# G021.net
KiCad netlist of a schematic drawn in EAGLE
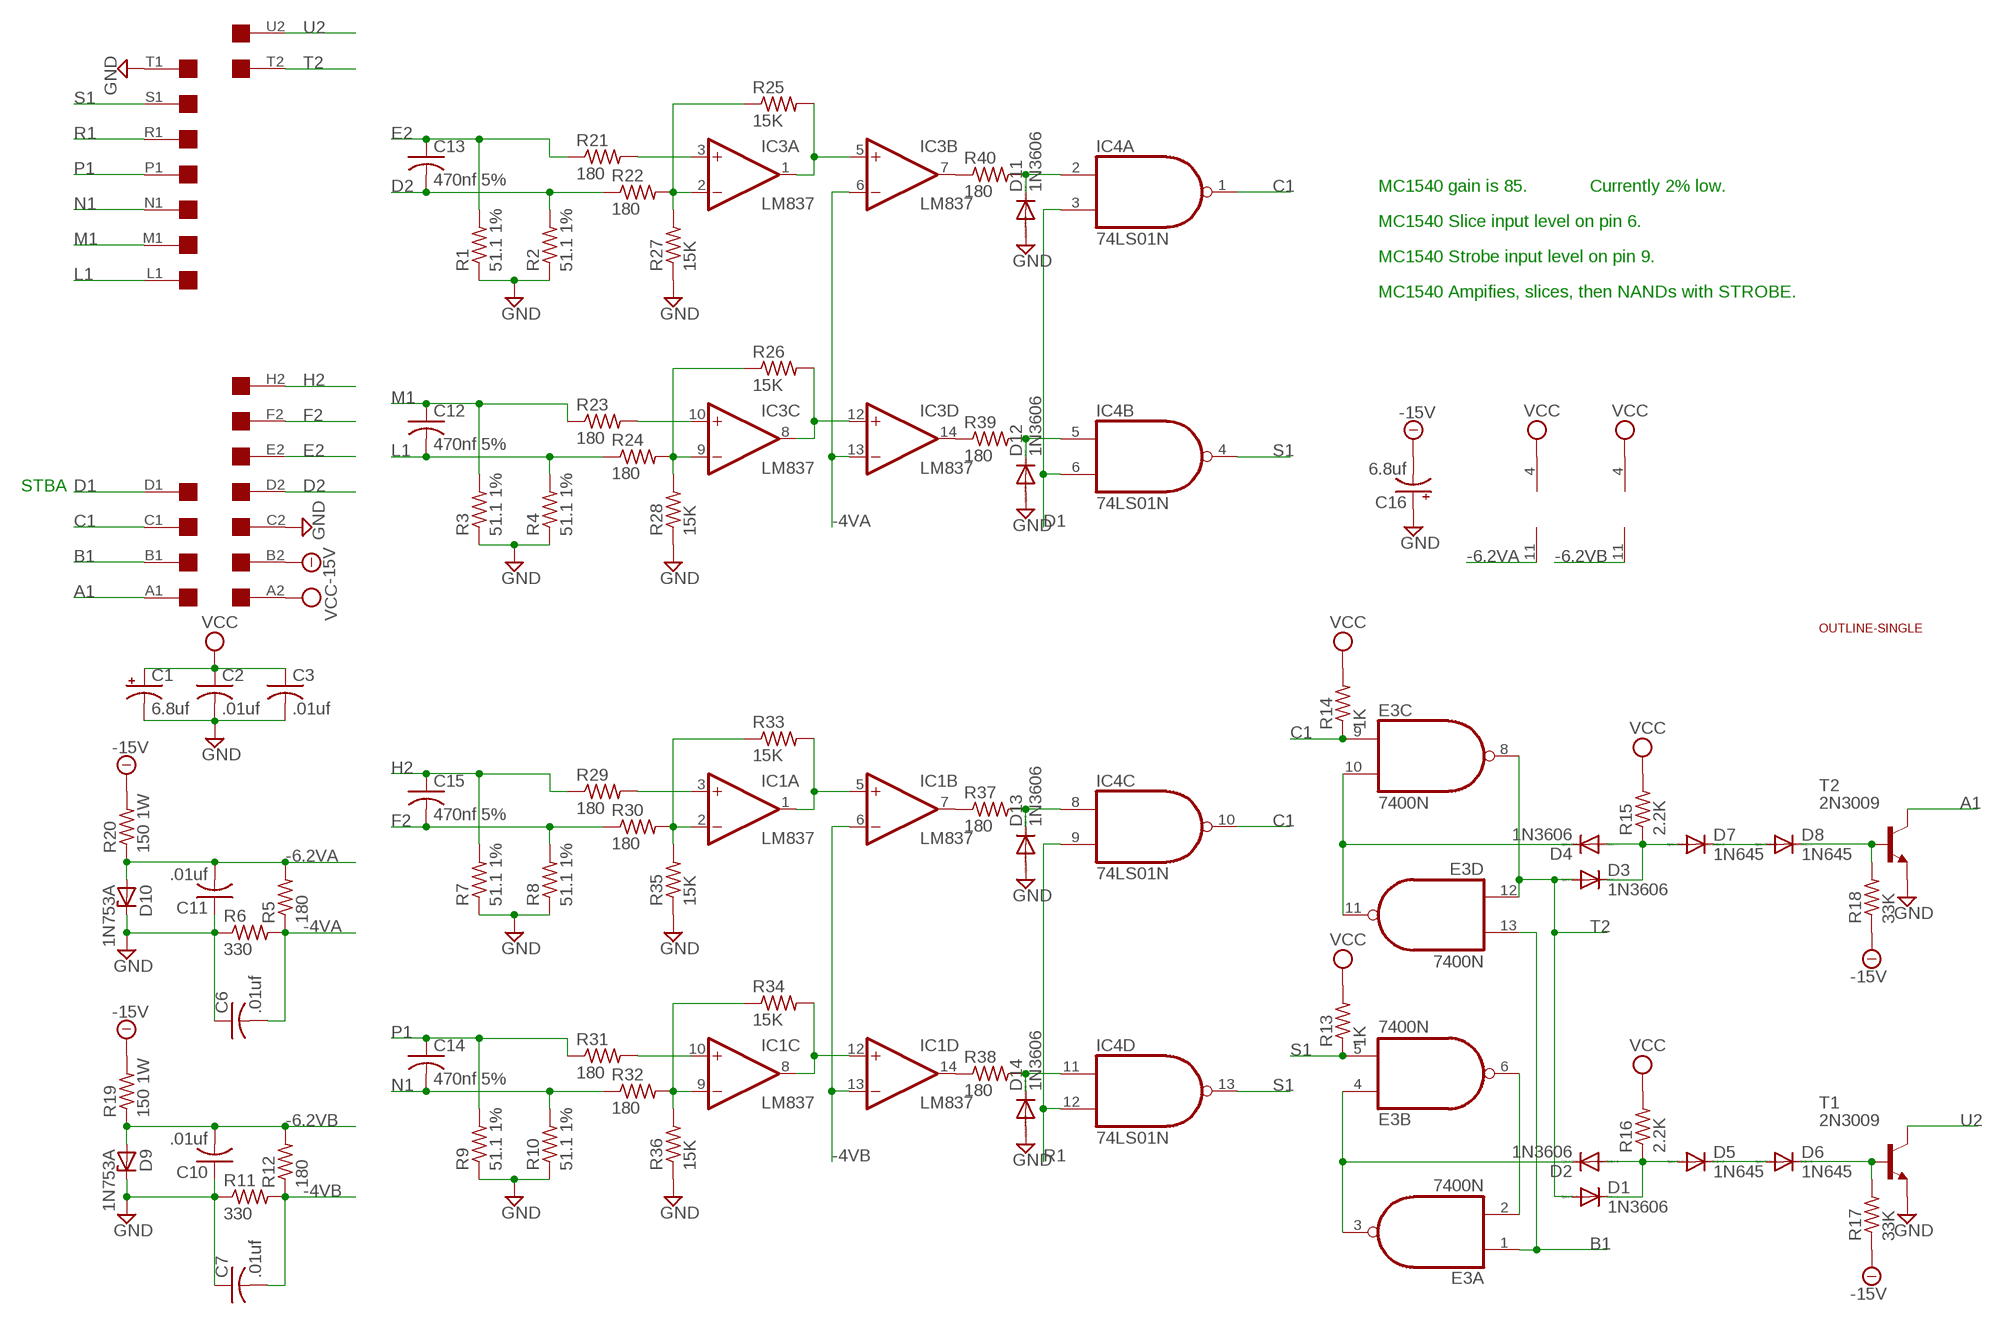
[diagram p0: schematic, sheet 1]

(export (version "E")
  (design (tool "Eeschema 10.0.6"))
  (components
    (comp (ref "C1")
      (value "6.8uf")
      (footprint "eagle-import:E15-5")
      (libsource (lib "eagle-import") (part "CPOL-USE15-5AXIAL"))
    )
    (comp (ref "C2")
      (value ".01uf")
      (footprint "eagle-import:C050-025X075")
      (libsource (lib "eagle-import") (part "C-US050-025X075"))
    )
    (comp (ref "C3")
      (value ".01uf")
      (footprint "eagle-import:C050-025X075")
      (libsource (lib "eagle-import") (part "C-US050-025X075"))
    )
    (comp (ref "C6")
      (value ".01uf")
      (footprint "eagle-import:C050-025X075")
      (libsource (lib "eagle-import") (part "C-US050-025X075"))
    )
    (comp (ref "C7")
      (value ".01uf")
      (footprint "eagle-import:C050-025X075")
      (libsource (lib "eagle-import") (part "C-US050-025X075"))
    )
    (comp (ref "C10")
      (value ".01uf")
      (footprint "eagle-import:C050-025X075")
      (libsource (lib "eagle-import") (part "C-US050-025X075"))
    )
    (comp (ref "C11")
      (value ".01uf")
      (footprint "eagle-import:C050-025X075")
      (libsource (lib "eagle-import") (part "C-US050-025X075"))
    )
    (comp (ref "C12")
      (value "470nf 5%")
      (footprint "eagle-import:C050-025X075")
      (libsource (lib "eagle-import") (part "C-US050-025X075"))
    )
    (comp (ref "C13")
      (value "470nf 5%")
      (footprint "eagle-import:C050-025X075")
      (libsource (lib "eagle-import") (part "C-US050-025X075"))
    )
    (comp (ref "C14")
      (value "470nf 5%")
      (footprint "eagle-import:C050-025X075")
      (libsource (lib "eagle-import") (part "C-US050-025X075"))
    )
    (comp (ref "C15")
      (value "470nf 5%")
      (footprint "eagle-import:C050-025X075")
      (libsource (lib "eagle-import") (part "C-US050-025X075"))
    )
    (comp (ref "C16")
      (value "6.8uf")
      (footprint "eagle-import:E15-5")
      (libsource (lib "eagle-import") (part "CPOL-USE15-5AXIAL"))
    )
    (comp (ref "D1")
      (value "1N3606")
      (footprint "eagle-import:DO35-10")
      (libsource (lib "eagle-import") (part "1N4148DO35-10"))
    )
    (comp (ref "D2")
      (value "1N3606")
      (footprint "eagle-import:DO35-10")
      (libsource (lib "eagle-import") (part "1N4148DO35-10"))
    )
    (comp (ref "D3")
      (value "1N3606")
      (footprint "eagle-import:DO35-10")
      (libsource (lib "eagle-import") (part "1N4148DO35-10"))
    )
    (comp (ref "D4")
      (value "1N3606")
      (footprint "eagle-import:DO35-10")
      (libsource (lib "eagle-import") (part "1N4148DO35-10"))
    )
    (comp (ref "D5")
      (value "1N645")
      (footprint "eagle-import:DO35-10")
      (libsource (lib "eagle-import") (part "1N4148DO35-10"))
    )
    (comp (ref "D6")
      (value "1N645")
      (footprint "eagle-import:DO35-10")
      (libsource (lib "eagle-import") (part "1N4148DO35-10"))
    )
    (comp (ref "D7")
      (value "1N645")
      (footprint "eagle-import:DO35-10")
      (libsource (lib "eagle-import") (part "1N4148DO35-10"))
    )
    (comp (ref "D8")
      (value "1N645")
      (footprint "eagle-import:DO35-10")
      (libsource (lib "eagle-import") (part "1N4148DO35-10"))
    )
    (comp (ref "D9")
      (value "1N753A")
      (footprint "eagle-import:F126Z10")
      (libsource (lib "eagle-import") (part "ZENER-DIODEF126-10"))
    )
    (comp (ref "D10")
      (value "1N753A")
      (footprint "eagle-import:F126Z10")
      (libsource (lib "eagle-import") (part "ZENER-DIODEF126-10"))
    )
    (comp (ref "D11")
      (value "1N3606")
      (footprint "eagle-import:DO35-10")
      (libsource (lib "eagle-import") (part "1N4148DO35-10"))
    )
    (comp (ref "D12")
      (value "1N3606")
      (footprint "eagle-import:DO35-10")
      (libsource (lib "eagle-import") (part "1N4148DO35-10"))
    )
    (comp (ref "D13")
      (value "1N3606")
      (footprint "eagle-import:DO35-10")
      (libsource (lib "eagle-import") (part "1N4148DO35-10"))
    )
    (comp (ref "D14")
      (value "1N3606")
      (footprint "eagle-import:DO35-10")
      (libsource (lib "eagle-import") (part "1N4148DO35-10"))
    )
    (comp (ref "E3")
      (value "7400N")
      (footprint "eagle-import:DIL14")
      (libsource (lib "eagle-import") (part "7400N"))
    )
    (comp (ref "IC1")
      (value "LM837")
      (footprint "eagle-import:DIL14")
      (libsource (lib "eagle-import") (part "OP11P"))
    )
    (comp (ref "IC3")
      (value "LM837")
      (footprint "eagle-import:DIL14")
      (libsource (lib "eagle-import") (part "OP11P"))
    )
    (comp (ref "IC4")
      (value "74LS01N")
      (footprint "eagle-import:DIL14")
      (libsource (lib "eagle-import") (part "7401NLS"))
    )
    (comp (ref "R1")
      (value "51.1 1%")
      (footprint "eagle-import:0207_10")
      (libsource (lib "eagle-import") (part "R-US_0207/10"))
    )
    (comp (ref "R2")
      (value "51.1 1%")
      (footprint "eagle-import:0207_10")
      (libsource (lib "eagle-import") (part "R-US_0207/10"))
    )
    (comp (ref "R3")
      (value "51.1 1%")
      (footprint "eagle-import:0207_10")
      (libsource (lib "eagle-import") (part "R-US_0207/10"))
    )
    (comp (ref "R4")
      (value "51.1 1%")
      (footprint "eagle-import:0207_10")
      (libsource (lib "eagle-import") (part "R-US_0207/10"))
    )
    (comp (ref "R5")
      (value "180")
      (footprint "eagle-import:0207_10")
      (libsource (lib "eagle-import") (part "R-US_0207/10"))
    )
    (comp (ref "R6")
      (value "330")
      (footprint "eagle-import:0207_10")
      (libsource (lib "eagle-import") (part "R-US_0207/10"))
    )
    (comp (ref "R7")
      (value "51.1 1%")
      (footprint "eagle-import:0207_10")
      (libsource (lib "eagle-import") (part "R-US_0207/10"))
    )
    (comp (ref "R8")
      (value "51.1 1%")
      (footprint "eagle-import:0207_10")
      (libsource (lib "eagle-import") (part "R-US_0207/10"))
    )
    (comp (ref "R9")
      (value "51.1 1%")
      (footprint "eagle-import:0207_10")
      (libsource (lib "eagle-import") (part "R-US_0207/10"))
    )
    (comp (ref "R10")
      (value "51.1 1%")
      (footprint "eagle-import:0207_10")
      (libsource (lib "eagle-import") (part "R-US_0207/10"))
    )
    (comp (ref "R11")
      (value "330")
      (footprint "eagle-import:0207_10")
      (libsource (lib "eagle-import") (part "R-US_0207/10"))
    )
    (comp (ref "R12")
      (value "180")
      (footprint "eagle-import:0207_10")
      (libsource (lib "eagle-import") (part "R-US_0207/10"))
    )
    (comp (ref "R13")
      (value "1K")
      (footprint "eagle-import:0207_10")
      (libsource (lib "eagle-import") (part "R-US_0207/10"))
    )
    (comp (ref "R14")
      (value "1K")
      (footprint "eagle-import:0207_10")
      (libsource (lib "eagle-import") (part "R-US_0207/10"))
    )
    (comp (ref "R15")
      (value "2.2K")
      (footprint "eagle-import:0207_10")
      (libsource (lib "eagle-import") (part "R-US_0207/10"))
    )
    (comp (ref "R16")
      (value "2.2K")
      (footprint "eagle-import:0207_10")
      (libsource (lib "eagle-import") (part "R-US_0207/10"))
    )
    (comp (ref "R17")
      (value "33K")
      (footprint "eagle-import:0207_10")
      (libsource (lib "eagle-import") (part "R-US_0207/10"))
    )
    (comp (ref "R18")
      (value "33K")
      (footprint "eagle-import:0207_10")
      (libsource (lib "eagle-import") (part "R-US_0207/10"))
    )
    (comp (ref "R19")
      (value "150 1W")
      (footprint "eagle-import:0414_15")
      (libsource (lib "eagle-import") (part "R-US_0414/15"))
    )
    (comp (ref "R20")
      (value "150 1W")
      (footprint "eagle-import:0414_15")
      (libsource (lib "eagle-import") (part "R-US_0414/15"))
    )
    (comp (ref "R21")
      (value "180")
      (footprint "eagle-import:0207_10")
      (libsource (lib "eagle-import") (part "R-US_0207/10"))
    )
    (comp (ref "R22")
      (value "180")
      (footprint "eagle-import:0207_10")
      (libsource (lib "eagle-import") (part "R-US_0207/10"))
    )
    (comp (ref "R23")
      (value "180")
      (footprint "eagle-import:0207_10")
      (libsource (lib "eagle-import") (part "R-US_0207/10"))
    )
    (comp (ref "R24")
      (value "180")
      (footprint "eagle-import:0207_10")
      (libsource (lib "eagle-import") (part "R-US_0207/10"))
    )
    (comp (ref "R25")
      (value "15K")
      (footprint "eagle-import:0207_10")
      (libsource (lib "eagle-import") (part "R-US_0207/10"))
    )
    (comp (ref "R26")
      (value "15K")
      (footprint "eagle-import:0207_10")
      (libsource (lib "eagle-import") (part "R-US_0207/10"))
    )
    (comp (ref "R27")
      (value "15K")
      (footprint "eagle-import:0207_10")
      (libsource (lib "eagle-import") (part "R-US_0207/10"))
    )
    (comp (ref "R28")
      (value "15K")
      (footprint "eagle-import:0207_10")
      (libsource (lib "eagle-import") (part "R-US_0207/10"))
    )
    (comp (ref "R29")
      (value "180")
      (footprint "eagle-import:0207_10")
      (libsource (lib "eagle-import") (part "R-US_0207/10"))
    )
    (comp (ref "R30")
      (value "180")
      (footprint "eagle-import:0207_10")
      (libsource (lib "eagle-import") (part "R-US_0207/10"))
    )
    (comp (ref "R31")
      (value "180")
      (footprint "eagle-import:0207_10")
      (libsource (lib "eagle-import") (part "R-US_0207/10"))
    )
    (comp (ref "R32")
      (value "180")
      (footprint "eagle-import:0207_10")
      (libsource (lib "eagle-import") (part "R-US_0207/10"))
    )
    (comp (ref "R33")
      (value "15K")
      (footprint "eagle-import:0207_10")
      (libsource (lib "eagle-import") (part "R-US_0207/10"))
    )
    (comp (ref "R34")
      (value "15K")
      (footprint "eagle-import:0207_10")
      (libsource (lib "eagle-import") (part "R-US_0207/10"))
    )
    (comp (ref "R35")
      (value "15K")
      (footprint "eagle-import:0207_10")
      (libsource (lib "eagle-import") (part "R-US_0207/10"))
    )
    (comp (ref "R36")
      (value "15K")
      (footprint "eagle-import:0207_10")
      (libsource (lib "eagle-import") (part "R-US_0207/10"))
    )
    (comp (ref "R37")
      (value "180")
      (footprint "eagle-import:0207_10")
      (libsource (lib "eagle-import") (part "R-US_0207/10"))
    )
    (comp (ref "R38")
      (value "180")
      (footprint "eagle-import:0207_10")
      (libsource (lib "eagle-import") (part "R-US_0207/10"))
    )
    (comp (ref "R39")
      (value "180")
      (footprint "eagle-import:0207_10")
      (libsource (lib "eagle-import") (part "R-US_0207/10"))
    )
    (comp (ref "R40")
      (value "180")
      (footprint "eagle-import:0207_10")
      (libsource (lib "eagle-import") (part "R-US_0207/10"))
    )
    (comp (ref "T1")
      (value "2N3009")
      (footprint "eagle-import:TO92")
      (libsource (lib "eagle-import") (part "2N3565"))
    )
    (comp (ref "T2")
      (value "2N3009")
      (footprint "eagle-import:TO92")
      (libsource (lib "eagle-import") (part "2N3565"))
    )
    (comp (ref "U$1")
      (value "SINGLE")
      (footprint "eagle-import:EDGE-CON2")
      (libsource (lib "eagle-import") (part "SINGLE"))
    )
    (comp (ref "U$2")
      (value "OUTLINE-SINGLE")
      (footprint "eagle-import:SINGLE")
      (libsource (lib "eagle-import") (part "OUTLINE-SINGLE"))
    )
  )
  (nets
    (net (code "1") (name "-15V") (class "Default")
      (node (ref "C16") (pin "-") (pinfunction "-_-") (pintype "passive"))
      (node (ref "R17") (pin "1") (pinfunction "1_1") (pintype "passive"))
      (node (ref "R18") (pin "1") (pinfunction "1_1") (pintype "passive"))
      (node (ref "R19") (pin "2") (pinfunction "2_2") (pintype "passive"))
      (node (ref "R20") (pin "2") (pinfunction "2_2") (pintype "passive"))
      (node (ref "U$1") (pin "B2") (pinfunction "1_B2") (pintype "bidirectional"))
    )
    (net (code "2") (name "/-4VA") (class "Default")
      (node (ref "C6") (pin "2") (pinfunction "2_2") (pintype "passive"))
      (node (ref "IC3") (pin "13") (pinfunction "-IN_13") (pintype "input"))
      (node (ref "IC3") (pin "6") (pinfunction "-IN_6") (pintype "input"))
      (node (ref "R5") (pin "1") (pinfunction "1_1") (pintype "passive"))
      (node (ref "R6") (pin "2") (pinfunction "2_2") (pintype "passive"))
    )
    (net (code "3") (name "/-4VB") (class "Default")
      (node (ref "C7") (pin "2") (pinfunction "2_2") (pintype "passive"))
      (node (ref "IC1") (pin "13") (pinfunction "-IN_13") (pintype "input"))
      (node (ref "IC1") (pin "6") (pinfunction "-IN_6") (pintype "input"))
      (node (ref "R11") (pin "2") (pinfunction "2_2") (pintype "passive"))
      (node (ref "R12") (pin "1") (pinfunction "1_1") (pintype "passive"))
    )
    (net (code "4") (name "/-6.2VA") (class "Default")
      (node (ref "C11") (pin "2") (pinfunction "2_2") (pintype "passive"))
      (node (ref "D10") (pin "A") (pinfunction "A_A") (pintype "passive"))
      (node (ref "IC3") (pin "11") (pinfunction "V-_11") (pintype "power_in"))
      (node (ref "R20") (pin "1") (pinfunction "1_1") (pintype "passive"))
      (node (ref "R5") (pin "2") (pinfunction "2_2") (pintype "passive"))
    )
    (net (code "5") (name "/-6.2VB") (class "Default")
      (node (ref "C10") (pin "2") (pinfunction "2_2") (pintype "passive"))
      (node (ref "D9") (pin "A") (pinfunction "A_A") (pintype "passive"))
      (node (ref "IC1") (pin "11") (pinfunction "V-_11") (pintype "power_in"))
      (node (ref "R12") (pin "2") (pinfunction "2_2") (pintype "passive"))
      (node (ref "R19") (pin "1") (pinfunction "1_1") (pintype "passive"))
    )
    (net (code "6") (name "/A1") (class "Default")
      (node (ref "T2") (pin "1") (pinfunction "C_1") (pintype "passive"))
      (node (ref "U$1") (pin "A1") (pinfunction "1_A1") (pintype "bidirectional"))
    )
    (net (code "7") (name "/B1") (class "Default")
      (node (ref "E3") (pin "1") (pinfunction "I0_1") (pintype "input"))
      (node (ref "E3") (pin "13") (pinfunction "I1_13") (pintype "input"))
      (node (ref "U$1") (pin "B1") (pinfunction "1_B1") (pintype "bidirectional"))
    )
    (net (code "8") (name "/C1") (class "Default")
      (node (ref "E3") (pin "9") (pinfunction "I0_9") (pintype "input"))
      (node (ref "IC4") (pin "1") (pinfunction "O_1") (pintype "open_collector"))
      (node (ref "IC4") (pin "10") (pinfunction "O_10") (pintype "open_collector"))
      (node (ref "R14") (pin "1") (pinfunction "1_1") (pintype "passive"))
      (node (ref "U$1") (pin "C1") (pinfunction "1_C1") (pintype "bidirectional"))
    )
    (net (code "9") (name "/D1") (class "Default")
      (node (ref "IC4") (pin "3") (pinfunction "I1_3") (pintype "input"))
      (node (ref "IC4") (pin "6") (pinfunction "I1_6") (pintype "input"))
      (node (ref "U$1") (pin "D1") (pinfunction "1_D1") (pintype "bidirectional"))
    )
    (net (code "10") (name "/D2") (class "Default")
      (node (ref "C13") (pin "2") (pinfunction "2_2") (pintype "passive"))
      (node (ref "R2") (pin "2") (pinfunction "2_2") (pintype "passive"))
      (node (ref "R22") (pin "1") (pinfunction "1_1") (pintype "passive"))
      (node (ref "U$1") (pin "D2") (pinfunction "1_D2") (pintype "bidirectional"))
    )
    (net (code "11") (name "/E2") (class "Default")
      (node (ref "C13") (pin "1") (pinfunction "1_1") (pintype "passive"))
      (node (ref "R1") (pin "2") (pinfunction "2_2") (pintype "passive"))
      (node (ref "R21") (pin "1") (pinfunction "1_1") (pintype "passive"))
      (node (ref "U$1") (pin "E2") (pinfunction "1_E2") (pintype "bidirectional"))
    )
    (net (code "12") (name "/F2") (class "Default")
      (node (ref "C15") (pin "2") (pinfunction "2_2") (pintype "passive"))
      (node (ref "R30") (pin "1") (pinfunction "1_1") (pintype "passive"))
      (node (ref "R8") (pin "2") (pinfunction "2_2") (pintype "passive"))
      (node (ref "U$1") (pin "F2") (pinfunction "1_F2") (pintype "bidirectional"))
    )
    (net (code "13") (name "/H2") (class "Default")
      (node (ref "C15") (pin "1") (pinfunction "1_1") (pintype "passive"))
      (node (ref "R29") (pin "1") (pinfunction "1_1") (pintype "passive"))
      (node (ref "R7") (pin "2") (pinfunction "2_2") (pintype "passive"))
      (node (ref "U$1") (pin "H2") (pinfunction "1_H2") (pintype "bidirectional"))
    )
    (net (code "14") (name "/L1") (class "Default")
      (node (ref "C12") (pin "2") (pinfunction "2_2") (pintype "passive"))
      (node (ref "R24") (pin "1") (pinfunction "1_1") (pintype "passive"))
      (node (ref "R4") (pin "2") (pinfunction "2_2") (pintype "passive"))
      (node (ref "U$1") (pin "L1") (pinfunction "1_L1") (pintype "bidirectional"))
    )
    (net (code "15") (name "/M1") (class "Default")
      (node (ref "C12") (pin "1") (pinfunction "1_1") (pintype "passive"))
      (node (ref "R23") (pin "1") (pinfunction "1_1") (pintype "passive"))
      (node (ref "R3") (pin "2") (pinfunction "2_2") (pintype "passive"))
      (node (ref "U$1") (pin "M1") (pinfunction "1_M1") (pintype "bidirectional"))
    )
    (net (code "16") (name "/N1") (class "Default")
      (node (ref "C14") (pin "2") (pinfunction "2_2") (pintype "passive"))
      (node (ref "R10") (pin "2") (pinfunction "2_2") (pintype "passive"))
      (node (ref "R32") (pin "1") (pinfunction "1_1") (pintype "passive"))
      (node (ref "U$1") (pin "N1") (pinfunction "1_N1") (pintype "bidirectional"))
    )
    (net (code "17") (name "/P1") (class "Default")
      (node (ref "C14") (pin "1") (pinfunction "1_1") (pintype "passive"))
      (node (ref "R31") (pin "1") (pinfunction "1_1") (pintype "passive"))
      (node (ref "R9") (pin "2") (pinfunction "2_2") (pintype "passive"))
      (node (ref "U$1") (pin "P1") (pinfunction "1_P1") (pintype "bidirectional"))
    )
    (net (code "18") (name "/R1") (class "Default")
      (node (ref "IC4") (pin "12") (pinfunction "I1_12") (pintype "input"))
      (node (ref "IC4") (pin "9") (pinfunction "I1_9") (pintype "input"))
      (node (ref "U$1") (pin "R1") (pinfunction "1_R1") (pintype "bidirectional"))
    )
    (net (code "19") (name "/S1") (class "Default")
      (node (ref "E3") (pin "5") (pinfunction "I1_5") (pintype "input"))
      (node (ref "IC4") (pin "13") (pinfunction "O_13") (pintype "open_collector"))
      (node (ref "IC4") (pin "4") (pinfunction "O_4") (pintype "open_collector"))
      (node (ref "R13") (pin "1") (pinfunction "1_1") (pintype "passive"))
      (node (ref "U$1") (pin "S1") (pinfunction "1_S1") (pintype "bidirectional"))
    )
    (net (code "20") (name "/T2") (class "Default")
      (node (ref "D1") (pin "A") (pinfunction "A_A") (pintype "passive"))
      (node (ref "D3") (pin "A") (pinfunction "A_A") (pintype "passive"))
      (node (ref "E3") (pin "12") (pinfunction "I0_12") (pintype "input"))
      (node (ref "E3") (pin "8") (pinfunction "O_8") (pintype "output"))
      (node (ref "U$1") (pin "T2") (pinfunction "1_T2") (pintype "bidirectional"))
    )
    (net (code "21") (name "/U2") (class "Default")
      (node (ref "T1") (pin "1") (pinfunction "C_1") (pintype "passive"))
      (node (ref "U$1") (pin "U2") (pinfunction "1_U2") (pintype "bidirectional"))
    )
    (net (code "22") (name "GND") (class "Default")
      (node (ref "C1") (pin "-") (pinfunction "-_-") (pintype "passive"))
      (node (ref "C10") (pin "1") (pinfunction "1_1") (pintype "passive"))
      (node (ref "C11") (pin "1") (pinfunction "1_1") (pintype "passive"))
      (node (ref "C16") (pin "+") (pinfunction "+_+") (pintype "passive"))
      (node (ref "C2") (pin "2") (pinfunction "2_2") (pintype "passive"))
      (node (ref "C3") (pin "2") (pinfunction "2_2") (pintype "passive"))
      (node (ref "C6") (pin "1") (pinfunction "1_1") (pintype "passive"))
      (node (ref "C7") (pin "1") (pinfunction "1_1") (pintype "passive"))
      (node (ref "D10") (pin "C") (pinfunction "C_C") (pintype "passive"))
      (node (ref "D11") (pin "A") (pinfunction "A_A") (pintype "passive"))
      (node (ref "D12") (pin "A") (pinfunction "A_A") (pintype "passive"))
      (node (ref "D13") (pin "A") (pinfunction "A_A") (pintype "passive"))
      (node (ref "D14") (pin "A") (pinfunction "A_A") (pintype "passive"))
      (node (ref "D9") (pin "C") (pinfunction "C_C") (pintype "passive"))
      (node (ref "R1") (pin "1") (pinfunction "1_1") (pintype "passive"))
      (node (ref "R10") (pin "1") (pinfunction "1_1") (pintype "passive"))
      (node (ref "R11") (pin "1") (pinfunction "1_1") (pintype "passive"))
      (node (ref "R2") (pin "1") (pinfunction "1_1") (pintype "passive"))
      (node (ref "R27") (pin "1") (pinfunction "1_1") (pintype "passive"))
      (node (ref "R28") (pin "1") (pinfunction "1_1") (pintype "passive"))
      (node (ref "R3") (pin "1") (pinfunction "1_1") (pintype "passive"))
      (node (ref "R35") (pin "1") (pinfunction "1_1") (pintype "passive"))
      (node (ref "R36") (pin "1") (pinfunction "1_1") (pintype "passive"))
      (node (ref "R4") (pin "1") (pinfunction "1_1") (pintype "passive"))
      (node (ref "R6") (pin "1") (pinfunction "1_1") (pintype "passive"))
      (node (ref "R7") (pin "1") (pinfunction "1_1") (pintype "passive"))
      (node (ref "R8") (pin "1") (pinfunction "1_1") (pintype "passive"))
      (node (ref "R9") (pin "1") (pinfunction "1_1") (pintype "passive"))
      (node (ref "T1") (pin "3") (pinfunction "E_3") (pintype "passive"))
      (node (ref "T2") (pin "3") (pinfunction "E_3") (pintype "passive"))
      (node (ref "U$1") (pin "C2") (pinfunction "1_C2") (pintype "bidirectional"))
      (node (ref "U$1") (pin "T1") (pinfunction "1_T1") (pintype "bidirectional"))
    )
    (net (code "23") (name "Net-(D1-PadC)") (class "Default")
      (node (ref "D1") (pin "C") (pinfunction "C_C") (pintype "passive"))
      (node (ref "D2") (pin "A") (pinfunction "A_A") (pintype "passive"))
      (node (ref "D5") (pin "A") (pinfunction "A_A") (pintype "passive"))
      (node (ref "R16") (pin "1") (pinfunction "1_1") (pintype "passive"))
    )
    (net (code "24") (name "Net-(D3-PadC)") (class "Default")
      (node (ref "D3") (pin "C") (pinfunction "C_C") (pintype "passive"))
      (node (ref "D4") (pin "A") (pinfunction "A_A") (pintype "passive"))
      (node (ref "D7") (pin "A") (pinfunction "A_A") (pintype "passive"))
      (node (ref "R15") (pin "1") (pinfunction "1_1") (pintype "passive"))
    )
    (net (code "25") (name "Net-(D5-PadC)") (class "Default")
      (node (ref "D5") (pin "C") (pinfunction "C_C") (pintype "passive"))
      (node (ref "D6") (pin "A") (pinfunction "A_A") (pintype "passive"))
    )
    (net (code "26") (name "Net-(D7-PadC)") (class "Default")
      (node (ref "D7") (pin "C") (pinfunction "C_C") (pintype "passive"))
      (node (ref "D8") (pin "A") (pinfunction "A_A") (pintype "passive"))
    )
    (net (code "27") (name "Net-(E3A-I1)") (class "Default")
      (node (ref "E3") (pin "2") (pinfunction "I1_2") (pintype "input"))
      (node (ref "E3") (pin "6") (pinfunction "O_6") (pintype "output"))
    )
    (net (code "28") (name "Net-(E3A-O)") (class "Default")
      (node (ref "D2") (pin "C") (pinfunction "C_C") (pintype "passive"))
      (node (ref "E3") (pin "3") (pinfunction "O_3") (pintype "output"))
      (node (ref "E3") (pin "4") (pinfunction "I0_4") (pintype "input"))
    )
    (net (code "29") (name "Net-(E3C-I1)") (class "Default")
      (node (ref "D4") (pin "C") (pinfunction "C_C") (pintype "passive"))
      (node (ref "E3") (pin "10") (pinfunction "I1_10") (pintype "input"))
      (node (ref "E3") (pin "11") (pinfunction "O_11") (pintype "output"))
    )
    (net (code "30") (name "Net-(IC1A-+IN)") (class "Default")
      (node (ref "IC1") (pin "3") (pinfunction "+IN_3") (pintype "input"))
      (node (ref "R29") (pin "2") (pinfunction "2_2") (pintype "passive"))
    )
    (net (code "31") (name "Net-(IC1A--IN)") (class "Default")
      (node (ref "IC1") (pin "2") (pinfunction "-IN_2") (pintype "input"))
      (node (ref "R30") (pin "2") (pinfunction "2_2") (pintype "passive"))
      (node (ref "R33") (pin "1") (pinfunction "1_1") (pintype "passive"))
      (node (ref "R35") (pin "2") (pinfunction "2_2") (pintype "passive"))
    )
    (net (code "32") (name "Net-(IC1A-OUT)") (class "Default")
      (node (ref "IC1") (pin "1") (pinfunction "OUT_1") (pintype "output"))
      (node (ref "IC1") (pin "5") (pinfunction "+IN_5") (pintype "input"))
      (node (ref "R33") (pin "2") (pinfunction "2_2") (pintype "passive"))
    )
    (net (code "33") (name "Net-(IC1B-OUT)") (class "Default")
      (node (ref "IC1") (pin "7") (pinfunction "OUT_7") (pintype "output"))
      (node (ref "R37") (pin "1") (pinfunction "1_1") (pintype "passive"))
    )
    (net (code "34") (name "Net-(IC1C-+IN)") (class "Default")
      (node (ref "IC1") (pin "10") (pinfunction "+IN_10") (pintype "input"))
      (node (ref "R31") (pin "2") (pinfunction "2_2") (pintype "passive"))
    )
    (net (code "35") (name "Net-(IC1C--IN)") (class "Default")
      (node (ref "IC1") (pin "9") (pinfunction "-IN_9") (pintype "input"))
      (node (ref "R32") (pin "2") (pinfunction "2_2") (pintype "passive"))
      (node (ref "R34") (pin "1") (pinfunction "1_1") (pintype "passive"))
      (node (ref "R36") (pin "2") (pinfunction "2_2") (pintype "passive"))
    )
    (net (code "36") (name "Net-(IC1C-OUT)") (class "Default")
      (node (ref "IC1") (pin "12") (pinfunction "+IN_12") (pintype "input"))
      (node (ref "IC1") (pin "8") (pinfunction "OUT_8") (pintype "output"))
      (node (ref "R34") (pin "2") (pinfunction "2_2") (pintype "passive"))
    )
    (net (code "37") (name "Net-(IC1D-OUT)") (class "Default")
      (node (ref "IC1") (pin "14") (pinfunction "OUT_14") (pintype "output"))
      (node (ref "R38") (pin "1") (pinfunction "1_1") (pintype "passive"))
    )
    (net (code "38") (name "Net-(IC3A-+IN)") (class "Default")
      (node (ref "IC3") (pin "3") (pinfunction "+IN_3") (pintype "input"))
      (node (ref "R21") (pin "2") (pinfunction "2_2") (pintype "passive"))
    )
    (net (code "39") (name "Net-(IC3A--IN)") (class "Default")
      (node (ref "IC3") (pin "2") (pinfunction "-IN_2") (pintype "input"))
      (node (ref "R22") (pin "2") (pinfunction "2_2") (pintype "passive"))
      (node (ref "R25") (pin "1") (pinfunction "1_1") (pintype "passive"))
      (node (ref "R27") (pin "2") (pinfunction "2_2") (pintype "passive"))
    )
    (net (code "40") (name "Net-(IC3A-OUT)") (class "Default")
      (node (ref "IC3") (pin "1") (pinfunction "OUT_1") (pintype "output"))
      (node (ref "IC3") (pin "5") (pinfunction "+IN_5") (pintype "input"))
      (node (ref "R25") (pin "2") (pinfunction "2_2") (pintype "passive"))
    )
    (net (code "41") (name "Net-(IC3B-OUT)") (class "Default")
      (node (ref "IC3") (pin "7") (pinfunction "OUT_7") (pintype "output"))
      (node (ref "R40") (pin "1") (pinfunction "1_1") (pintype "passive"))
    )
    (net (code "42") (name "Net-(IC3C-+IN)") (class "Default")
      (node (ref "IC3") (pin "10") (pinfunction "+IN_10") (pintype "input"))
      (node (ref "R23") (pin "2") (pinfunction "2_2") (pintype "passive"))
    )
    (net (code "43") (name "Net-(IC3C--IN)") (class "Default")
      (node (ref "IC3") (pin "9") (pinfunction "-IN_9") (pintype "input"))
      (node (ref "R24") (pin "2") (pinfunction "2_2") (pintype "passive"))
      (node (ref "R26") (pin "1") (pinfunction "1_1") (pintype "passive"))
      (node (ref "R28") (pin "2") (pinfunction "2_2") (pintype "passive"))
    )
    (net (code "44") (name "Net-(IC3C-OUT)") (class "Default")
      (node (ref "IC3") (pin "12") (pinfunction "+IN_12") (pintype "input"))
      (node (ref "IC3") (pin "8") (pinfunction "OUT_8") (pintype "output"))
      (node (ref "R26") (pin "2") (pinfunction "2_2") (pintype "passive"))
    )
    (net (code "45") (name "Net-(IC3D-OUT)") (class "Default")
      (node (ref "IC3") (pin "14") (pinfunction "OUT_14") (pintype "output"))
      (node (ref "R39") (pin "1") (pinfunction "1_1") (pintype "passive"))
    )
    (net (code "46") (name "Net-(IC4A-I0)") (class "Default")
      (node (ref "D11") (pin "C") (pinfunction "C_C") (pintype "passive"))
      (node (ref "IC4") (pin "2") (pinfunction "I0_2") (pintype "input"))
      (node (ref "R40") (pin "2") (pinfunction "2_2") (pintype "passive"))
    )
    (net (code "47") (name "Net-(IC4B-I0)") (class "Default")
      (node (ref "D12") (pin "C") (pinfunction "C_C") (pintype "passive"))
      (node (ref "IC4") (pin "5") (pinfunction "I0_5") (pintype "input"))
      (node (ref "R39") (pin "2") (pinfunction "2_2") (pintype "passive"))
    )
    (net (code "48") (name "Net-(IC4C-I0)") (class "Default")
      (node (ref "D13") (pin "C") (pinfunction "C_C") (pintype "passive"))
      (node (ref "IC4") (pin "8") (pinfunction "I0_8") (pintype "input"))
      (node (ref "R37") (pin "2") (pinfunction "2_2") (pintype "passive"))
    )
    (net (code "49") (name "Net-(IC4D-I0)") (class "Default")
      (node (ref "D14") (pin "C") (pinfunction "C_C") (pintype "passive"))
      (node (ref "IC4") (pin "11") (pinfunction "I0_11") (pintype "input"))
      (node (ref "R38") (pin "2") (pinfunction "2_2") (pintype "passive"))
    )
    (net (code "50") (name "Net-(T1-B)") (class "Default")
      (node (ref "D6") (pin "C") (pinfunction "C_C") (pintype "passive"))
      (node (ref "R17") (pin "2") (pinfunction "2_2") (pintype "passive"))
      (node (ref "T1") (pin "2") (pinfunction "B_2") (pintype "passive"))
    )
    (net (code "51") (name "Net-(T2-B)") (class "Default")
      (node (ref "D8") (pin "C") (pinfunction "C_C") (pintype "passive"))
      (node (ref "R18") (pin "2") (pinfunction "2_2") (pintype "passive"))
      (node (ref "T2") (pin "2") (pinfunction "B_2") (pintype "passive"))
    )
    (net (code "52") (name "VCC") (class "Default")
      (node (ref "C1") (pin "+") (pinfunction "+_+") (pintype "passive"))
      (node (ref "C2") (pin "1") (pinfunction "1_1") (pintype "passive"))
      (node (ref "C3") (pin "1") (pinfunction "1_1") (pintype "passive"))
      (node (ref "IC1") (pin "4") (pinfunction "V+_4") (pintype "power_in"))
      (node (ref "IC3") (pin "4") (pinfunction "V+_4") (pintype "power_in"))
      (node (ref "R13") (pin "2") (pinfunction "2_2") (pintype "passive"))
      (node (ref "R14") (pin "2") (pinfunction "2_2") (pintype "passive"))
      (node (ref "R15") (pin "2") (pinfunction "2_2") (pintype "passive"))
      (node (ref "R16") (pin "2") (pinfunction "2_2") (pintype "passive"))
      (node (ref "U$1") (pin "A2") (pinfunction "1_A2") (pintype "bidirectional"))
    )
  )
)
